# Slim-CC1101-NRF24L01-Adapter.net
KiCad netlist of a schematic drawn in EAGLE
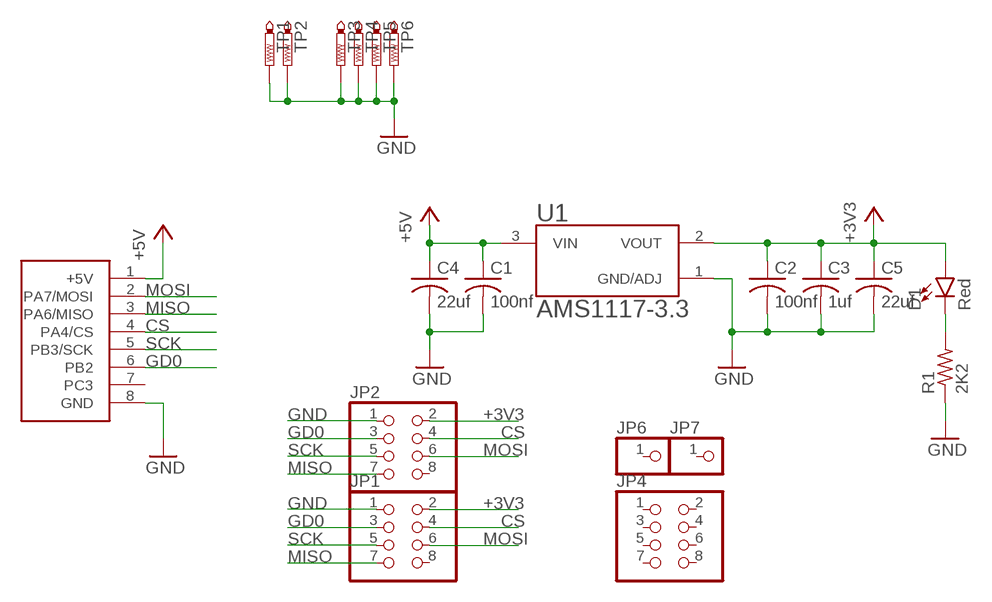
[diagram p0: schematic, sheet 1]

(export (version "E")
  (design (tool "Eeschema 10.0.6"))
  (components
    (comp (ref "C1")
      (value "100nf")
      (footprint "eagle-import:C0805")
      (libsource (lib "eagle-import") (part "C-USC0805"))
    )
    (comp (ref "C2")
      (value "100nf")
      (footprint "eagle-import:C0805")
      (libsource (lib "eagle-import") (part "C-USC0805"))
    )
    (comp (ref "C3")
      (value "1uf")
      (footprint "eagle-import:C0805")
      (libsource (lib "eagle-import") (part "C-USC0805"))
    )
    (comp (ref "C4")
      (value "22uf")
      (footprint "eagle-import:C3216")
      (libsource (lib "eagle-import") (part "C-USC3216"))
    )
    (comp (ref "C5")
      (value "22uf")
      (footprint "eagle-import:C3216")
      (libsource (lib "eagle-import") (part "C-USC3216"))
    )
    (comp (ref "D1")
      (value "Red")
      (footprint "eagle-import:LED-1206")
      (libsource (lib "eagle-import") (part "LED-RED1206"))
    )
    (comp (ref "JP1")
      (value "PINHD-2X4")
      (footprint "eagle-import:2X04")
      (libsource (lib "eagle-import") (part "PINHD-2X4"))
    )
    (comp (ref "JP2")
      (value "PINHD-2X4")
      (footprint "eagle-import:2X04")
      (libsource (lib "eagle-import") (part "PINHD-2X4"))
    )
    (comp (ref "JP4")
      (value "PINHD-2X4")
      (footprint "eagle-import:2X04")
      (libsource (lib "eagle-import") (part "PINHD-2X4"))
    )
    (comp (ref "JP6")
      (value "PINHD-1X1")
      (footprint "eagle-import:1X01")
      (libsource (lib "eagle-import") (part "PINHD-1X1"))
    )
    (comp (ref "JP7")
      (value "PINHD-1X1")
      (footprint "eagle-import:1X01")
      (libsource (lib "eagle-import") (part "PINHD-1X1"))
    )
    (comp (ref "R1")
      (value "2K2")
      (footprint "eagle-import:R0805")
      (libsource (lib "eagle-import") (part "R-US_R0805"))
    )
    (comp (ref "TP1")
      (value "PTR1B1,27")
      (footprint "eagle-import:B1,27")
      (libsource (lib "eagle-import") (part "PTR1B1,27"))
    )
    (comp (ref "TP2")
      (value "PTR1B1,27")
      (footprint "eagle-import:B1,27")
      (libsource (lib "eagle-import") (part "PTR1B1,27"))
    )
    (comp (ref "TP3")
      (value "PTR1B2,54")
      (footprint "eagle-import:B2,54")
      (libsource (lib "eagle-import") (part "PTR1B2,54"))
    )
    (comp (ref "TP4")
      (value "PTR1B2,54")
      (footprint "eagle-import:B2,54")
      (libsource (lib "eagle-import") (part "PTR1B2,54"))
    )
    (comp (ref "TP5")
      (value "PTR1B2,54")
      (footprint "eagle-import:B2,54")
      (libsource (lib "eagle-import") (part "PTR1B2,54"))
    )
    (comp (ref "TP6")
      (value "PTR1B2,54")
      (footprint "eagle-import:B2,54")
      (libsource (lib "eagle-import") (part "PTR1B2,54"))
    )
    (comp (ref "U$1")
      (value "LEFT-H1-SMD")
      (footprint "eagle-import:LEFT-H1-SMD")
      (libsource (lib "eagle-import") (part "LEFT-H1-SMD"))
    )
    (comp (ref "U1")
      (value "AMS1117-3.3")
      (footprint "eagle-import:SOT229P700X180-4N")
      (fields (field (name "MF") "Advanced Monolithic Systems"))
      (libsource (lib "eagle-import") (part "AMS1117-3.3"))
    )
  )
  (nets
    (net (code "1") (name "+3V3") (class "Default")
      (node (ref "C2") (pin "1") (pinfunction "1_1") (pintype "passive"))
      (node (ref "C3") (pin "1") (pinfunction "1_1") (pintype "passive"))
      (node (ref "C5") (pin "1") (pinfunction "1_1") (pintype "passive"))
      (node (ref "D1") (pin "A") (pinfunction "A_A") (pintype "passive"))
      (node (ref "JP1") (pin "2") (pinfunction "2_2") (pintype "passive"))
      (node (ref "JP2") (pin "2") (pinfunction "2_2") (pintype "passive"))
      (node (ref "U1") (pin "2") (pinfunction "VOUT_2") (pintype "output"))
    )
    (net (code "2") (name "+5V") (class "Default")
      (node (ref "C1") (pin "1") (pinfunction "1_1") (pintype "passive"))
      (node (ref "C4") (pin "1") (pinfunction "1_1") (pintype "passive"))
      (node (ref "U$1") (pin "1") (pinfunction "+5V_1") (pintype "bidirectional"))
      (node (ref "U1") (pin "3") (pinfunction "VIN_3") (pintype "input"))
    )
    (net (code "3") (name "/CS") (class "Default")
      (node (ref "JP1") (pin "4") (pinfunction "4_4") (pintype "passive"))
      (node (ref "JP2") (pin "4") (pinfunction "4_4") (pintype "passive"))
      (node (ref "U$1") (pin "4") (pinfunction "PA4/CS_4") (pintype "bidirectional"))
    )
    (net (code "4") (name "/GD0") (class "Default")
      (node (ref "JP1") (pin "3") (pinfunction "3_3") (pintype "passive"))
      (node (ref "JP2") (pin "3") (pinfunction "3_3") (pintype "passive"))
      (node (ref "U$1") (pin "6") (pinfunction "PB2_6") (pintype "bidirectional"))
    )
    (net (code "5") (name "/MISO") (class "Default")
      (node (ref "JP1") (pin "7") (pinfunction "7_7") (pintype "passive"))
      (node (ref "JP2") (pin "7") (pinfunction "7_7") (pintype "passive"))
      (node (ref "U$1") (pin "3") (pinfunction "PA6/MISO_3") (pintype "bidirectional"))
    )
    (net (code "6") (name "/MOSI") (class "Default")
      (node (ref "JP1") (pin "6") (pinfunction "6_6") (pintype "passive"))
      (node (ref "JP2") (pin "6") (pinfunction "6_6") (pintype "passive"))
      (node (ref "U$1") (pin "2") (pinfunction "PA7/MOSI_2") (pintype "bidirectional"))
    )
    (net (code "7") (name "/SCK") (class "Default")
      (node (ref "JP1") (pin "5") (pinfunction "5_5") (pintype "passive"))
      (node (ref "JP2") (pin "5") (pinfunction "5_5") (pintype "passive"))
      (node (ref "U$1") (pin "5") (pinfunction "PB3/SCK_5") (pintype "bidirectional"))
    )
    (net (code "8") (name "GND") (class "Default")
      (node (ref "C1") (pin "2") (pinfunction "2_2") (pintype "passive"))
      (node (ref "C2") (pin "2") (pinfunction "2_2") (pintype "passive"))
      (node (ref "C3") (pin "2") (pinfunction "2_2") (pintype "passive"))
      (node (ref "C4") (pin "2") (pinfunction "2_2") (pintype "passive"))
      (node (ref "C5") (pin "2") (pinfunction "2_2") (pintype "passive"))
      (node (ref "JP1") (pin "1") (pinfunction "1_1") (pintype "passive"))
      (node (ref "JP2") (pin "1") (pinfunction "1_1") (pintype "passive"))
      (node (ref "R1") (pin "1") (pinfunction "1_1") (pintype "passive"))
      (node (ref "TP1") (pin "TP") (pinfunction "TP_TP") (pintype "input"))
      (node (ref "TP2") (pin "TP") (pinfunction "TP_TP") (pintype "input"))
      (node (ref "TP3") (pin "TP") (pinfunction "TP_TP") (pintype "input"))
      (node (ref "TP4") (pin "TP") (pinfunction "TP_TP") (pintype "input"))
      (node (ref "TP5") (pin "TP") (pinfunction "TP_TP") (pintype "input"))
      (node (ref "TP6") (pin "TP") (pinfunction "TP_TP") (pintype "input"))
      (node (ref "U$1") (pin "8") (pinfunction "GND_8") (pintype "bidirectional"))
      (node (ref "U1") (pin "1") (pinfunction "GND/ADJ_1") (pintype "power_in"))
    )
    (net (code "9") (name "Net-(D1-PadC)") (class "Default")
      (node (ref "D1") (pin "C") (pinfunction "C_C") (pintype "passive"))
      (node (ref "R1") (pin "2") (pinfunction "2_2") (pintype "passive"))
    )
    (net (code "10") (name "unconnected-(JP1-Pad8)") (class "Default")
      (node (ref "JP1") (pin "8") (pinfunction "8_8") (pintype "passive"))
    )
    (net (code "11") (name "unconnected-(JP2-Pad8)") (class "Default")
      (node (ref "JP2") (pin "8") (pinfunction "8_8") (pintype "passive"))
    )
    (net (code "12") (name "unconnected-(JP4-Pad1)") (class "Default")
      (node (ref "JP4") (pin "1") (pinfunction "1_1") (pintype "passive"))
    )
    (net (code "13") (name "unconnected-(JP4-Pad2)") (class "Default")
      (node (ref "JP4") (pin "2") (pinfunction "2_2") (pintype "passive"))
    )
    (net (code "14") (name "unconnected-(JP4-Pad3)") (class "Default")
      (node (ref "JP4") (pin "3") (pinfunction "3_3") (pintype "passive"))
    )
    (net (code "15") (name "unconnected-(JP4-Pad4)") (class "Default")
      (node (ref "JP4") (pin "4") (pinfunction "4_4") (pintype "passive"))
    )
    (net (code "16") (name "unconnected-(JP4-Pad5)") (class "Default")
      (node (ref "JP4") (pin "5") (pinfunction "5_5") (pintype "passive"))
    )
    (net (code "17") (name "unconnected-(JP4-Pad6)") (class "Default")
      (node (ref "JP4") (pin "6") (pinfunction "6_6") (pintype "passive"))
    )
    (net (code "18") (name "unconnected-(JP4-Pad7)") (class "Default")
      (node (ref "JP4") (pin "7") (pinfunction "7_7") (pintype "passive"))
    )
    (net (code "19") (name "unconnected-(JP4-Pad8)") (class "Default")
      (node (ref "JP4") (pin "8") (pinfunction "8_8") (pintype "passive"))
    )
    (net (code "20") (name "unconnected-(JP6-Pad1)") (class "Default")
      (node (ref "JP6") (pin "1") (pinfunction "1_1") (pintype "passive"))
    )
    (net (code "21") (name "unconnected-(JP7-Pad1)") (class "Default")
      (node (ref "JP7") (pin "1") (pinfunction "1_1") (pintype "passive"))
    )
    (net (code "22") (name "unconnected-(U$1-PC3-Pad7)") (class "Default")
      (node (ref "U$1") (pin "7") (pinfunction "PC3_7") (pintype "bidirectional"))
    )
  )
)
